# MEP_SAO.net
KiCad netlist of a schematic drawn in EAGLE
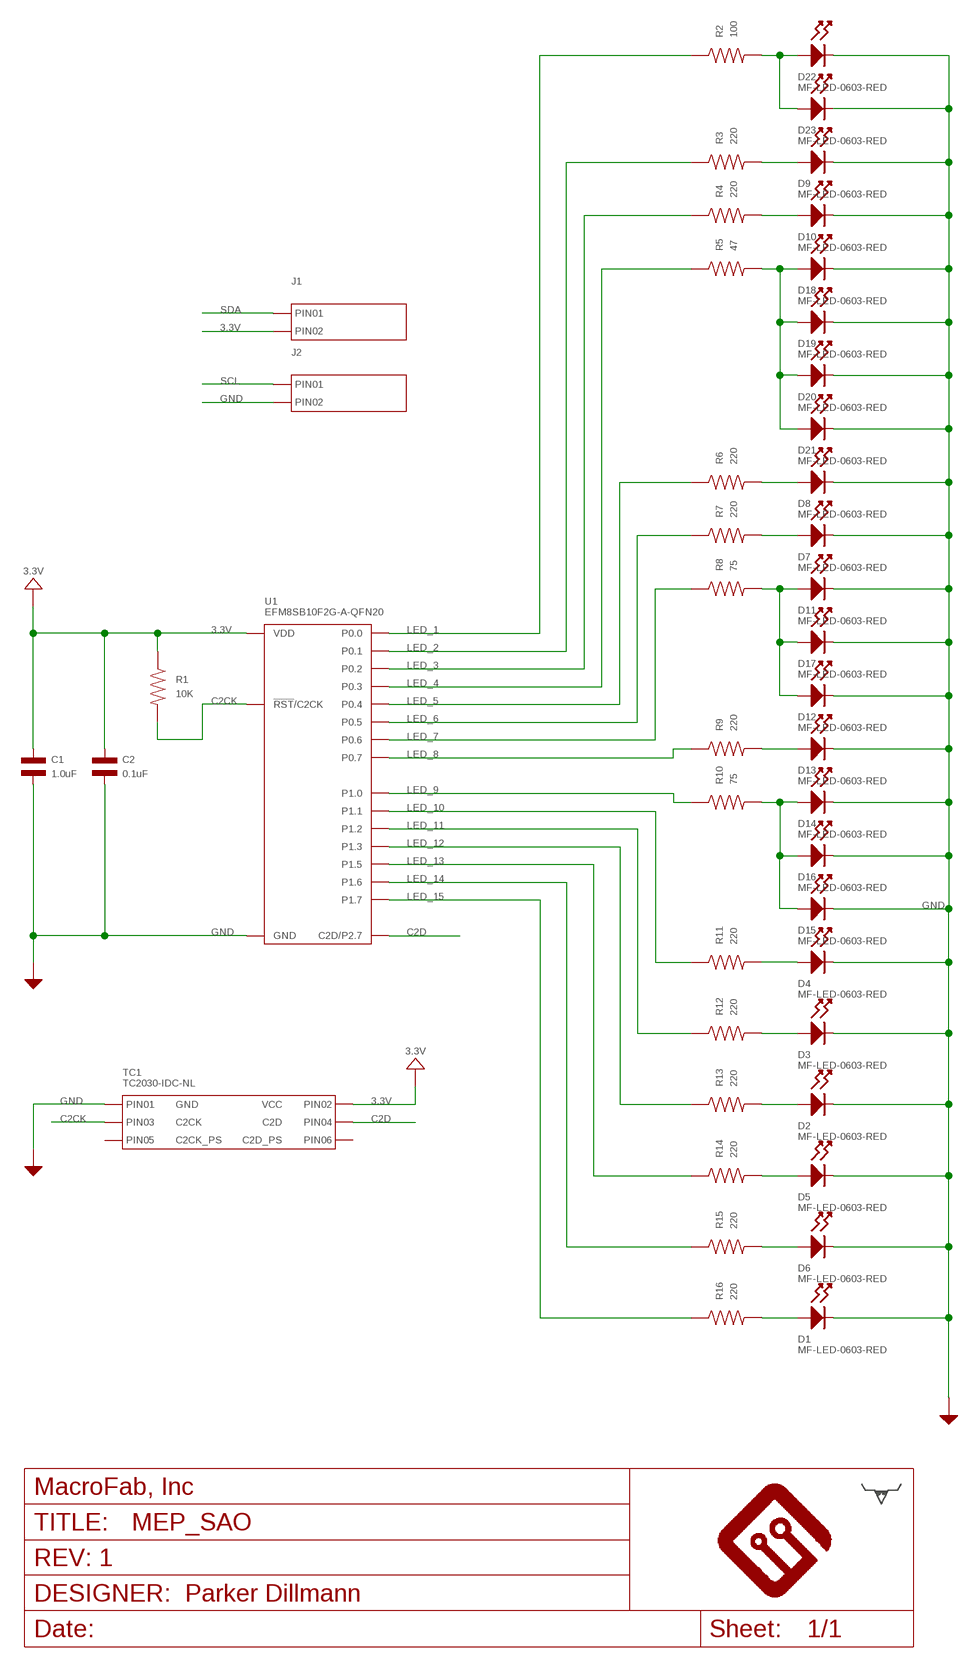
[diagram p0: schematic, sheet 1]

(export (version "E")
  (design (tool "Eeschema 10.0.6"))
  (components
    (comp (ref "C1")
      (value "1.0uF")
      (footprint "eagle-import:C0603")
      (fields (field (name "MPN") "MF-CAP-0603-1uF"))
      (libsource (lib "eagle-import") (part "CAPACITOR_NP_0603"))
    )
    (comp (ref "C2")
      (value "0.1uF")
      (footprint "eagle-import:C0603")
      (fields (field (name "MPN") "MF-CAP-0603-0.1uF"))
      (libsource (lib "eagle-import") (part "CAPACITOR_NP_0603"))
    )
    (comp (ref "D1")
      (value "MF-LED-0603-RED")
      (footprint "eagle-import:LED0603")
      (fields (field (name "HOUSEPART") "YES"))
      (libsource (lib "eagle-import") (part "LED_SINGLE-0603-RED"))
    )
    (comp (ref "D2")
      (value "MF-LED-0603-RED")
      (footprint "eagle-import:LED0603")
      (fields (field (name "HOUSEPART") "YES"))
      (libsource (lib "eagle-import") (part "LED_SINGLE-0603-RED"))
    )
    (comp (ref "D3")
      (value "MF-LED-0603-RED")
      (footprint "eagle-import:LED0603")
      (fields (field (name "HOUSEPART") "YES"))
      (libsource (lib "eagle-import") (part "LED_SINGLE-0603-RED"))
    )
    (comp (ref "D4")
      (value "MF-LED-0603-RED")
      (footprint "eagle-import:LED0603")
      (fields (field (name "HOUSEPART") "YES"))
      (libsource (lib "eagle-import") (part "LED_SINGLE-0603-RED"))
    )
    (comp (ref "D5")
      (value "MF-LED-0603-RED")
      (footprint "eagle-import:LED0603")
      (fields (field (name "HOUSEPART") "YES"))
      (libsource (lib "eagle-import") (part "LED_SINGLE-0603-RED"))
    )
    (comp (ref "D6")
      (value "MF-LED-0603-RED")
      (footprint "eagle-import:LED0603")
      (fields (field (name "HOUSEPART") "YES"))
      (libsource (lib "eagle-import") (part "LED_SINGLE-0603-RED"))
    )
    (comp (ref "D7")
      (value "MF-LED-0603-RED")
      (footprint "eagle-import:LED0603")
      (fields (field (name "HOUSEPART") "YES"))
      (libsource (lib "eagle-import") (part "LED_SINGLE-0603-RED"))
    )
    (comp (ref "D8")
      (value "MF-LED-0603-RED")
      (footprint "eagle-import:LED0603")
      (fields (field (name "HOUSEPART") "YES"))
      (libsource (lib "eagle-import") (part "LED_SINGLE-0603-RED"))
    )
    (comp (ref "D9")
      (value "MF-LED-0603-RED")
      (footprint "eagle-import:LED0603")
      (fields (field (name "HOUSEPART") "YES"))
      (libsource (lib "eagle-import") (part "LED_SINGLE-0603-RED"))
    )
    (comp (ref "D10")
      (value "MF-LED-0603-RED")
      (footprint "eagle-import:LED0603")
      (fields (field (name "HOUSEPART") "YES"))
      (libsource (lib "eagle-import") (part "LED_SINGLE-0603-RED"))
    )
    (comp (ref "D11")
      (value "MF-LED-0603-RED")
      (footprint "eagle-import:LED0603")
      (fields (field (name "HOUSEPART") "YES"))
      (libsource (lib "eagle-import") (part "LED_SINGLE-0603-RED"))
    )
    (comp (ref "D12")
      (value "MF-LED-0603-RED")
      (footprint "eagle-import:LED0603")
      (fields (field (name "HOUSEPART") "YES"))
      (libsource (lib "eagle-import") (part "LED_SINGLE-0603-RED"))
    )
    (comp (ref "D13")
      (value "MF-LED-0603-RED")
      (footprint "eagle-import:LED0603")
      (fields (field (name "HOUSEPART") "YES"))
      (libsource (lib "eagle-import") (part "LED_SINGLE-0603-RED"))
    )
    (comp (ref "D14")
      (value "MF-LED-0603-RED")
      (footprint "eagle-import:LED0603")
      (fields (field (name "HOUSEPART") "YES"))
      (libsource (lib "eagle-import") (part "LED_SINGLE-0603-RED"))
    )
    (comp (ref "D15")
      (value "MF-LED-0603-RED")
      (footprint "eagle-import:LED0603")
      (fields (field (name "HOUSEPART") "YES"))
      (libsource (lib "eagle-import") (part "LED_SINGLE-0603-RED"))
    )
    (comp (ref "D16")
      (value "MF-LED-0603-RED")
      (footprint "eagle-import:LED0603")
      (fields (field (name "HOUSEPART") "YES"))
      (libsource (lib "eagle-import") (part "LED_SINGLE-0603-RED"))
    )
    (comp (ref "D17")
      (value "MF-LED-0603-RED")
      (footprint "eagle-import:LED0603")
      (fields (field (name "HOUSEPART") "YES"))
      (libsource (lib "eagle-import") (part "LED_SINGLE-0603-RED"))
    )
    (comp (ref "D18")
      (value "MF-LED-0603-RED")
      (footprint "eagle-import:LED0603")
      (fields (field (name "HOUSEPART") "YES"))
      (libsource (lib "eagle-import") (part "LED_SINGLE-0603-RED"))
    )
    (comp (ref "D19")
      (value "MF-LED-0603-RED")
      (footprint "eagle-import:LED0603")
      (fields (field (name "HOUSEPART") "YES"))
      (libsource (lib "eagle-import") (part "LED_SINGLE-0603-RED"))
    )
    (comp (ref "D20")
      (value "MF-LED-0603-RED")
      (footprint "eagle-import:LED0603")
      (fields (field (name "HOUSEPART") "YES"))
      (libsource (lib "eagle-import") (part "LED_SINGLE-0603-RED"))
    )
    (comp (ref "D21")
      (value "MF-LED-0603-RED")
      (footprint "eagle-import:LED0603")
      (fields (field (name "HOUSEPART") "YES"))
      (libsource (lib "eagle-import") (part "LED_SINGLE-0603-RED"))
    )
    (comp (ref "D22")
      (value "MF-LED-0603-RED")
      (footprint "eagle-import:LED0603")
      (fields (field (name "HOUSEPART") "YES"))
      (libsource (lib "eagle-import") (part "LED_SINGLE-0603-RED"))
    )
    (comp (ref "D23")
      (value "MF-LED-0603-RED")
      (footprint "eagle-import:LED0603")
      (fields (field (name "HOUSEPART") "YES"))
      (libsource (lib "eagle-import") (part "LED_SINGLE-0603-RED"))
    )
    (comp (ref "FRAME1")
      (value "MF_FRAMEDEFAULT")
      (footprint "eagle-import:MF_FRAME_DEFAULT")
      (fields
        (field (name "HOUSEPART") "0")
        (field (name "DNAME") "Parker Dillmann")
        (field (name "REVNUM") "REV: 1")
      )
      (libsource (lib "eagle-import") (part "MF_FRAMEDEFAULT"))
    )
    (comp (ref "J1")
      (value "CON_01X02_2.54MM_PIN_HEADER")
      (footprint "eagle-import:2.54MM_01X02_PIN_HEADER")
      (fields (field (name "POPULATE") "0"))
      (libsource (lib "eagle-import") (part "CON_01X02_2.54MM_PIN_HEADER"))
    )
    (comp (ref "J2")
      (value "CON_01X02_2.54MM_PIN_HEADER")
      (footprint "eagle-import:2.54MM_01X02_PIN_HEADER")
      (fields (field (name "POPULATE") "0"))
      (libsource (lib "eagle-import") (part "CON_01X02_2.54MM_PIN_HEADER"))
    )
    (comp (ref "R1")
      (value "10K")
      (footprint "eagle-import:R0402")
      (fields (field (name "MPN") "MF-RES-0402-10K"))
      (libsource (lib "eagle-import") (part "RESISTOR_0402"))
    )
    (comp (ref "R2")
      (value "100")
      (footprint "eagle-import:R0402")
      (fields (field (name "MPN") "MF-RES-0402-100"))
      (libsource (lib "eagle-import") (part "RESISTOR_0402"))
    )
    (comp (ref "R3")
      (value "220")
      (footprint "eagle-import:R0402")
      (fields (field (name "MPN") "MF-RES-0402-220"))
      (libsource (lib "eagle-import") (part "RESISTOR_0402"))
    )
    (comp (ref "R4")
      (value "220")
      (footprint "eagle-import:R0402")
      (fields (field (name "MPN") "MF-RES-0402-220"))
      (libsource (lib "eagle-import") (part "RESISTOR_0402"))
    )
    (comp (ref "R5")
      (value "47")
      (footprint "eagle-import:R0402")
      (fields (field (name "MPN") "MF-RES-0402-47"))
      (libsource (lib "eagle-import") (part "RESISTOR_0402"))
    )
    (comp (ref "R6")
      (value "220")
      (footprint "eagle-import:R0402")
      (fields (field (name "MPN") "MF-RES-0402-220"))
      (libsource (lib "eagle-import") (part "RESISTOR_0402"))
    )
    (comp (ref "R7")
      (value "220")
      (footprint "eagle-import:R0402")
      (fields (field (name "MPN") "MF-RES-0402-220"))
      (libsource (lib "eagle-import") (part "RESISTOR_0402"))
    )
    (comp (ref "R8")
      (value "75")
      (footprint "eagle-import:R0402")
      (fields (field (name "MPN") "MF-RES-0402-75"))
      (libsource (lib "eagle-import") (part "RESISTOR_0402"))
    )
    (comp (ref "R9")
      (value "220")
      (footprint "eagle-import:R0402")
      (fields (field (name "MPN") "MF-RES-0402-220"))
      (libsource (lib "eagle-import") (part "RESISTOR_0402"))
    )
    (comp (ref "R10")
      (value "75")
      (footprint "eagle-import:R0402")
      (fields (field (name "MPN") "MF-RES-0402-75"))
      (libsource (lib "eagle-import") (part "RESISTOR_0402"))
    )
    (comp (ref "R11")
      (value "220")
      (footprint "eagle-import:R0402")
      (fields (field (name "MPN") "MF-RES-0402-220"))
      (libsource (lib "eagle-import") (part "RESISTOR_0402"))
    )
    (comp (ref "R12")
      (value "220")
      (footprint "eagle-import:R0402")
      (fields (field (name "MPN") "MF-RES-0402-220"))
      (libsource (lib "eagle-import") (part "RESISTOR_0402"))
    )
    (comp (ref "R13")
      (value "220")
      (footprint "eagle-import:R0402")
      (fields (field (name "MPN") "MF-RES-0402-220"))
      (libsource (lib "eagle-import") (part "RESISTOR_0402"))
    )
    (comp (ref "R14")
      (value "220")
      (footprint "eagle-import:R0402")
      (fields (field (name "MPN") "MF-RES-0402-220"))
      (libsource (lib "eagle-import") (part "RESISTOR_0402"))
    )
    (comp (ref "R15")
      (value "220")
      (footprint "eagle-import:R0402")
      (fields (field (name "MPN") "MF-RES-0402-220"))
      (libsource (lib "eagle-import") (part "RESISTOR_0402"))
    )
    (comp (ref "R16")
      (value "220")
      (footprint "eagle-import:R0402")
      (fields (field (name "MPN") "MF-RES-0402-220"))
      (libsource (lib "eagle-import") (part "RESISTOR_0402"))
    )
    (comp (ref "TC1")
      (value "TC2030-IDC-NL")
      (footprint "eagle-import:TC2030-IDC-NL")
      (fields (field (name "HOUSEPART") "NO"))
      (libsource (lib "eagle-import") (part "CON_02X03_TC2030-IDC-NL_SILABS2TC"))
    )
    (comp (ref "U$6")
      (value "LHE_LOGOLHE_LOGO")
      (footprint "eagle-import:LHE_LOGO")
      (libsource (lib "eagle-import") (part "LHE_LOGOLHE_LOGO"))
    )
    (comp (ref "U1")
      (value "EFM8SB10F2G-A-QFN20")
      (footprint "eagle-import:EFM8SB10F(2_4_8)G-A-QFN20")
      (fields (field (name "HOUSEPART") "NO"))
      (libsource (lib "eagle-import") (part "EFM8SB10F(2/4/8)G-A-QFN20"))
    )
  )
  (nets
    (net (code "1") (name "/C2CK") (class "Default")
      (node (ref "R1") (pin "P$2") (pinfunction "P$2_P$2") (pintype "passive"))
      (node (ref "TC1") (pin "P$3") (pinfunction "PIN3_P$3") (pintype "bidirectional"))
      (node (ref "U1") (pin "P$5") (pinfunction "~{RST}/C2CK_P$5") (pintype "bidirectional"))
    )
    (net (code "2") (name "/C2D") (class "Default")
      (node (ref "TC1") (pin "P$4") (pinfunction "PIN4_P$4") (pintype "bidirectional"))
      (node (ref "U1") (pin "P$6") (pinfunction "C2D/P2.7_P$6") (pintype "bidirectional"))
    )
    (net (code "3") (name "/LED_1") (class "Default")
      (node (ref "R2") (pin "P$1") (pinfunction "P$1_P$1") (pintype "passive"))
      (node (ref "U1") (pin "P$2") (pinfunction "P0.0_P$2") (pintype "bidirectional"))
    )
    (net (code "4") (name "/LED_2") (class "Default")
      (node (ref "R3") (pin "P$1") (pinfunction "P$1_P$1") (pintype "passive"))
      (node (ref "U1") (pin "P$1") (pinfunction "P0.1_P$1") (pintype "bidirectional"))
    )
    (net (code "5") (name "/LED_3") (class "Default")
      (node (ref "R4") (pin "P$1") (pinfunction "P$1_P$1") (pintype "passive"))
      (node (ref "U1") (pin "P$20") (pinfunction "P0.2_P$20") (pintype "bidirectional"))
    )
    (net (code "6") (name "/LED_4") (class "Default")
      (node (ref "R5") (pin "P$1") (pinfunction "P$1_P$1") (pintype "passive"))
      (node (ref "U1") (pin "P$19") (pinfunction "P0.3_P$19") (pintype "bidirectional"))
    )
    (net (code "7") (name "/LED_5") (class "Default")
      (node (ref "R6") (pin "P$1") (pinfunction "P$1_P$1") (pintype "passive"))
      (node (ref "U1") (pin "P$18") (pinfunction "P0.4_P$18") (pintype "bidirectional"))
    )
    (net (code "8") (name "/LED_6") (class "Default")
      (node (ref "R7") (pin "P$1") (pinfunction "P$1_P$1") (pintype "passive"))
      (node (ref "U1") (pin "P$17") (pinfunction "P0.5_P$17") (pintype "bidirectional"))
    )
    (net (code "9") (name "/LED_7") (class "Default")
      (node (ref "R8") (pin "P$1") (pinfunction "P$1_P$1") (pintype "passive"))
      (node (ref "U1") (pin "P$16") (pinfunction "P0.6_P$16") (pintype "bidirectional"))
    )
    (net (code "10") (name "/LED_8") (class "Default")
      (node (ref "R9") (pin "P$1") (pinfunction "P$1_P$1") (pintype "passive"))
      (node (ref "U1") (pin "P$15") (pinfunction "P0.7_P$15") (pintype "bidirectional"))
    )
    (net (code "11") (name "/LED_9") (class "Default")
      (node (ref "R10") (pin "P$1") (pinfunction "P$1_P$1") (pintype "passive"))
      (node (ref "U1") (pin "P$14") (pinfunction "P1.0_P$14") (pintype "bidirectional"))
    )
    (net (code "12") (name "/LED_10") (class "Default")
      (node (ref "R11") (pin "P$1") (pinfunction "P$1_P$1") (pintype "passive"))
      (node (ref "U1") (pin "P$13") (pinfunction "P1.1_P$13") (pintype "bidirectional"))
    )
    (net (code "13") (name "/LED_11") (class "Default")
      (node (ref "R12") (pin "P$1") (pinfunction "P$1_P$1") (pintype "passive"))
      (node (ref "U1") (pin "P$11") (pinfunction "P1.2_P$11") (pintype "bidirectional"))
    )
    (net (code "14") (name "/LED_12") (class "Default")
      (node (ref "R13") (pin "P$1") (pinfunction "P$1_P$1") (pintype "passive"))
      (node (ref "U1") (pin "P$10") (pinfunction "P1.3_P$10") (pintype "bidirectional"))
    )
    (net (code "15") (name "/LED_13") (class "Default")
      (node (ref "R14") (pin "P$1") (pinfunction "P$1_P$1") (pintype "passive"))
      (node (ref "U1") (pin "P$9") (pinfunction "P1.5_P$9") (pintype "bidirectional"))
    )
    (net (code "16") (name "/LED_14") (class "Default")
      (node (ref "R15") (pin "P$1") (pinfunction "P$1_P$1") (pintype "passive"))
      (node (ref "U1") (pin "P$8") (pinfunction "P1.6_P$8") (pintype "bidirectional"))
    )
    (net (code "17") (name "/LED_15") (class "Default")
      (node (ref "R16") (pin "P$1") (pinfunction "P$1_P$1") (pintype "passive"))
      (node (ref "U1") (pin "P$7") (pinfunction "P1.7_P$7") (pintype "bidirectional"))
    )
    (net (code "18") (name "/SCL") (class "Default")
      (node (ref "J2") (pin "1") (pinfunction "PIN1_1") (pintype "bidirectional"))
    )
    (net (code "19") (name "/SDA") (class "Default")
      (node (ref "J1") (pin "1") (pinfunction "PIN1_1") (pintype "bidirectional"))
    )
    (net (code "20") (name "3.3V") (class "Default")
      (node (ref "C1") (pin "P$1") (pinfunction "P$1_P$1") (pintype "passive"))
      (node (ref "C2") (pin "P$1") (pinfunction "P$1_P$1") (pintype "passive"))
      (node (ref "J1") (pin "2") (pinfunction "PIN2_2") (pintype "bidirectional"))
      (node (ref "R1") (pin "P$1") (pinfunction "P$1_P$1") (pintype "passive"))
      (node (ref "TC1") (pin "P$2") (pinfunction "PIN2_P$2") (pintype "bidirectional"))
      (node (ref "U1") (pin "P$4") (pinfunction "VDD_P$4") (pintype "bidirectional"))
    )
    (net (code "21") (name "GND_RAIL") (class "Default")
      (node (ref "C1") (pin "P$2") (pinfunction "P$2_P$2") (pintype "passive"))
      (node (ref "C2") (pin "P$2") (pinfunction "P$2_P$2") (pintype "passive"))
      (node (ref "D1") (pin "CATHODE") (pinfunction "CATHODE_CATHODE") (pintype "power_in"))
      (node (ref "D10") (pin "CATHODE") (pinfunction "CATHODE_CATHODE") (pintype "power_in"))
      (node (ref "D11") (pin "CATHODE") (pinfunction "CATHODE_CATHODE") (pintype "power_in"))
      (node (ref "D12") (pin "CATHODE") (pinfunction "CATHODE_CATHODE") (pintype "power_in"))
      (node (ref "D13") (pin "CATHODE") (pinfunction "CATHODE_CATHODE") (pintype "power_in"))
      (node (ref "D14") (pin "CATHODE") (pinfunction "CATHODE_CATHODE") (pintype "power_in"))
      (node (ref "D15") (pin "CATHODE") (pinfunction "CATHODE_CATHODE") (pintype "power_in"))
      (node (ref "D16") (pin "CATHODE") (pinfunction "CATHODE_CATHODE") (pintype "power_in"))
      (node (ref "D17") (pin "CATHODE") (pinfunction "CATHODE_CATHODE") (pintype "power_in"))
      (node (ref "D18") (pin "CATHODE") (pinfunction "CATHODE_CATHODE") (pintype "power_in"))
      (node (ref "D19") (pin "CATHODE") (pinfunction "CATHODE_CATHODE") (pintype "power_in"))
      (node (ref "D2") (pin "CATHODE") (pinfunction "CATHODE_CATHODE") (pintype "power_in"))
      (node (ref "D20") (pin "CATHODE") (pinfunction "CATHODE_CATHODE") (pintype "power_in"))
      (node (ref "D21") (pin "CATHODE") (pinfunction "CATHODE_CATHODE") (pintype "power_in"))
      (node (ref "D22") (pin "CATHODE") (pinfunction "CATHODE_CATHODE") (pintype "power_in"))
      (node (ref "D23") (pin "CATHODE") (pinfunction "CATHODE_CATHODE") (pintype "power_in"))
      (node (ref "D3") (pin "CATHODE") (pinfunction "CATHODE_CATHODE") (pintype "power_in"))
      (node (ref "D4") (pin "CATHODE") (pinfunction "CATHODE_CATHODE") (pintype "power_in"))
      (node (ref "D5") (pin "CATHODE") (pinfunction "CATHODE_CATHODE") (pintype "power_in"))
      (node (ref "D6") (pin "CATHODE") (pinfunction "CATHODE_CATHODE") (pintype "power_in"))
      (node (ref "D7") (pin "CATHODE") (pinfunction "CATHODE_CATHODE") (pintype "power_in"))
      (node (ref "D8") (pin "CATHODE") (pinfunction "CATHODE_CATHODE") (pintype "power_in"))
      (node (ref "D9") (pin "CATHODE") (pinfunction "CATHODE_CATHODE") (pintype "power_in"))
      (node (ref "J2") (pin "2") (pinfunction "PIN2_2") (pintype "bidirectional"))
      (node (ref "TC1") (pin "P$1") (pinfunction "PIN1_P$1") (pintype "bidirectional"))
      (node (ref "U1") (pin "P$12") (pinfunction "GND_P$12") (pintype "bidirectional"))
      (node (ref "U1") (pin "P$3") (pinfunction "GND_P$3") (pintype "bidirectional"))
      (node (ref "U1") (pin "PAD") (pinfunction "GND_PAD") (pintype "bidirectional"))
    )
    (net (code "22") (name "Net-(D1-PadANODE)") (class "Default")
      (node (ref "D1") (pin "ANODE") (pinfunction "ANODE_ANODE") (pintype "power_in"))
      (node (ref "R16") (pin "P$2") (pinfunction "P$2_P$2") (pintype "passive"))
    )
    (net (code "23") (name "Net-(D2-PadANODE)") (class "Default")
      (node (ref "D2") (pin "ANODE") (pinfunction "ANODE_ANODE") (pintype "power_in"))
      (node (ref "R13") (pin "P$2") (pinfunction "P$2_P$2") (pintype "passive"))
    )
    (net (code "24") (name "Net-(D3-PadANODE)") (class "Default")
      (node (ref "D3") (pin "ANODE") (pinfunction "ANODE_ANODE") (pintype "power_in"))
      (node (ref "R12") (pin "P$2") (pinfunction "P$2_P$2") (pintype "passive"))
    )
    (net (code "25") (name "Net-(D4-PadANODE)") (class "Default")
      (node (ref "D4") (pin "ANODE") (pinfunction "ANODE_ANODE") (pintype "power_in"))
      (node (ref "R11") (pin "P$2") (pinfunction "P$2_P$2") (pintype "passive"))
    )
    (net (code "26") (name "Net-(D5-PadANODE)") (class "Default")
      (node (ref "D5") (pin "ANODE") (pinfunction "ANODE_ANODE") (pintype "power_in"))
      (node (ref "R14") (pin "P$2") (pinfunction "P$2_P$2") (pintype "passive"))
    )
    (net (code "27") (name "Net-(D6-PadANODE)") (class "Default")
      (node (ref "D6") (pin "ANODE") (pinfunction "ANODE_ANODE") (pintype "power_in"))
      (node (ref "R15") (pin "P$2") (pinfunction "P$2_P$2") (pintype "passive"))
    )
    (net (code "28") (name "Net-(D7-PadANODE)") (class "Default")
      (node (ref "D7") (pin "ANODE") (pinfunction "ANODE_ANODE") (pintype "power_in"))
      (node (ref "R7") (pin "P$2") (pinfunction "P$2_P$2") (pintype "passive"))
    )
    (net (code "29") (name "Net-(D8-PadANODE)") (class "Default")
      (node (ref "D8") (pin "ANODE") (pinfunction "ANODE_ANODE") (pintype "power_in"))
      (node (ref "R6") (pin "P$2") (pinfunction "P$2_P$2") (pintype "passive"))
    )
    (net (code "30") (name "Net-(D9-PadANODE)") (class "Default")
      (node (ref "D9") (pin "ANODE") (pinfunction "ANODE_ANODE") (pintype "power_in"))
      (node (ref "R3") (pin "P$2") (pinfunction "P$2_P$2") (pintype "passive"))
    )
    (net (code "31") (name "Net-(D10-PadANODE)") (class "Default")
      (node (ref "D10") (pin "ANODE") (pinfunction "ANODE_ANODE") (pintype "power_in"))
      (node (ref "R4") (pin "P$2") (pinfunction "P$2_P$2") (pintype "passive"))
    )
    (net (code "32") (name "Net-(D11-PadANODE)") (class "Default")
      (node (ref "D11") (pin "ANODE") (pinfunction "ANODE_ANODE") (pintype "power_in"))
      (node (ref "D12") (pin "ANODE") (pinfunction "ANODE_ANODE") (pintype "power_in"))
      (node (ref "D17") (pin "ANODE") (pinfunction "ANODE_ANODE") (pintype "power_in"))
      (node (ref "R8") (pin "P$2") (pinfunction "P$2_P$2") (pintype "passive"))
    )
    (net (code "33") (name "Net-(D13-PadANODE)") (class "Default")
      (node (ref "D13") (pin "ANODE") (pinfunction "ANODE_ANODE") (pintype "power_in"))
      (node (ref "R9") (pin "P$2") (pinfunction "P$2_P$2") (pintype "passive"))
    )
    (net (code "34") (name "Net-(D14-PadANODE)") (class "Default")
      (node (ref "D14") (pin "ANODE") (pinfunction "ANODE_ANODE") (pintype "power_in"))
      (node (ref "D15") (pin "ANODE") (pinfunction "ANODE_ANODE") (pintype "power_in"))
      (node (ref "D16") (pin "ANODE") (pinfunction "ANODE_ANODE") (pintype "power_in"))
      (node (ref "R10") (pin "P$2") (pinfunction "P$2_P$2") (pintype "passive"))
    )
    (net (code "35") (name "Net-(D18-PadANODE)") (class "Default")
      (node (ref "D18") (pin "ANODE") (pinfunction "ANODE_ANODE") (pintype "power_in"))
      (node (ref "D19") (pin "ANODE") (pinfunction "ANODE_ANODE") (pintype "power_in"))
      (node (ref "D20") (pin "ANODE") (pinfunction "ANODE_ANODE") (pintype "power_in"))
      (node (ref "D21") (pin "ANODE") (pinfunction "ANODE_ANODE") (pintype "power_in"))
      (node (ref "R5") (pin "P$2") (pinfunction "P$2_P$2") (pintype "passive"))
    )
    (net (code "36") (name "Net-(D22-PadANODE)") (class "Default")
      (node (ref "D22") (pin "ANODE") (pinfunction "ANODE_ANODE") (pintype "power_in"))
      (node (ref "D23") (pin "ANODE") (pinfunction "ANODE_ANODE") (pintype "power_in"))
      (node (ref "R2") (pin "P$2") (pinfunction "P$2_P$2") (pintype "passive"))
    )
    (net (code "37") (name "unconnected-(TC1-PIN5-PadP$5)") (class "Default")
      (node (ref "TC1") (pin "P$5") (pinfunction "PIN5_P$5") (pintype "bidirectional"))
    )
    (net (code "38") (name "unconnected-(TC1-PIN6-PadP$6)") (class "Default")
      (node (ref "TC1") (pin "P$6") (pinfunction "PIN6_P$6") (pintype "bidirectional"))
    )
  )
)
